# eeprom_2layer.net
KiCad netlist of a schematic drawn in EAGLE
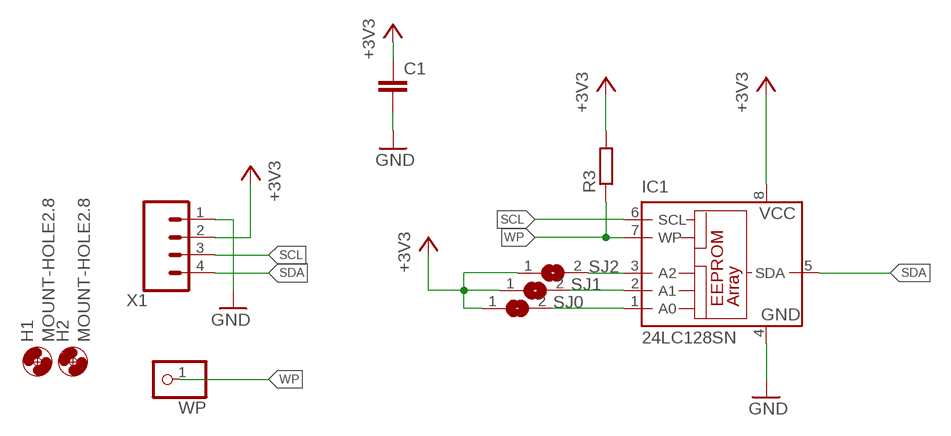
[diagram p0: schematic, sheet 1]

(export (version "E")
  (design (tool "Eeschema 10.0.6"))
  (components
    (comp (ref "C1")
      (value "C-EUC0805")
      (footprint "eagle-import:C0805")
      (libsource (lib "eagle-import") (part "C-EUC0805"))
    )
    (comp (ref "H1")
      (value "MOUNT-HOLE2.8")
      (footprint "eagle-import:2,8")
      (libsource (lib "eagle-import") (part "MOUNT-HOLE2.8"))
    )
    (comp (ref "H2")
      (value "MOUNT-HOLE2.8")
      (footprint "eagle-import:2,8")
      (libsource (lib "eagle-import") (part "MOUNT-HOLE2.8"))
    )
    (comp (ref "IC1")
      (value "24LC128SN")
      (footprint "eagle-import:SO-08")
      (fields (field (name "MF") "MICROCHIP") (field (name "MPN") "24LC128-I/SNG"))
      (libsource (lib "eagle-import") (part "24SNLC128"))
    )
    (comp (ref "R3")
      (value "R-EU_R0805")
      (footprint "eagle-import:R0805")
      (libsource (lib "eagle-import") (part "R-EU_R0805"))
    )
    (comp (ref "SJ0") (value "SJ") (footprint "eagle-import:SJ") (libsource (lib "eagle-import") (part "SJ")))
    (comp (ref "SJ1") (value "SJ") (footprint "eagle-import:SJ") (libsource (lib "eagle-import") (part "SJ")))
    (comp (ref "SJ2") (value "SJ") (footprint "eagle-import:SJ") (libsource (lib "eagle-import") (part "SJ")))
    (comp (ref "WP")
      (value "PINHD-1X1")
      (footprint "eagle-import:1X01")
      (libsource (lib "eagle-import") (part "PINHD-1X1"))
    )
    (comp (ref "X1")
      (value "JST-XH-04-PIN-ROUND-PAD")
      (footprint "eagle-import:JST-XH-04-PACKAGE-ROUND-PAD")
      (libsource (lib "eagle-import") (part "JST-XH-04-PIN-ROUND-PAD"))
    )
  )
  (nets
    (net (code "1") (name "+3V3") (class "Default")
      (node (ref "C1") (pin "1") (pinfunction "1_1") (pintype "passive"))
      (node (ref "IC1") (pin "8") (pinfunction "VCC_8") (pintype "power_in"))
      (node (ref "R3") (pin "2") (pinfunction "2_2") (pintype "passive"))
      (node (ref "SJ0") (pin "1") (pinfunction "1_1") (pintype "passive"))
      (node (ref "SJ1") (pin "1") (pinfunction "1_1") (pintype "passive"))
      (node (ref "SJ2") (pin "1") (pinfunction "1_1") (pintype "passive"))
      (node (ref "X1") (pin "2") (pinfunction "2_2") (pintype "passive"))
    )
    (net (code "2") (name "GND") (class "Default")
      (node (ref "C1") (pin "2") (pinfunction "2_2") (pintype "passive"))
      (node (ref "IC1") (pin "4") (pinfunction "GND_4") (pintype "power_in"))
      (node (ref "X1") (pin "1") (pinfunction "1_1") (pintype "passive"))
    )
    (net (code "3") (name "Net-(IC1-A0)") (class "Default")
      (node (ref "IC1") (pin "1") (pinfunction "A0_1") (pintype "input"))
      (node (ref "SJ0") (pin "2") (pinfunction "2_2") (pintype "passive"))
    )
    (net (code "4") (name "Net-(IC1-A1)") (class "Default")
      (node (ref "IC1") (pin "2") (pinfunction "A1_2") (pintype "input"))
      (node (ref "SJ1") (pin "2") (pinfunction "2_2") (pintype "passive"))
    )
    (net (code "5") (name "Net-(IC1-A2)") (class "Default")
      (node (ref "IC1") (pin "3") (pinfunction "A2_3") (pintype "input"))
      (node (ref "SJ2") (pin "2") (pinfunction "2_2") (pintype "passive"))
    )
    (net (code "6") (name "SCL") (class "Default")
      (node (ref "IC1") (pin "6") (pinfunction "SCL_6") (pintype "input"))
      (node (ref "X1") (pin "3") (pinfunction "3_3") (pintype "passive"))
    )
    (net (code "7") (name "SDA") (class "Default")
      (node (ref "IC1") (pin "5") (pinfunction "SDA_5") (pintype "bidirectional"))
      (node (ref "X1") (pin "4") (pinfunction "4_4") (pintype "passive"))
    )
    (net (code "8") (name "WP") (class "Default")
      (node (ref "IC1") (pin "7") (pinfunction "WP_7") (pintype "input"))
      (node (ref "R3") (pin "1") (pinfunction "1_1") (pintype "passive"))
      (node (ref "WP") (pin "1") (pinfunction "1_1") (pintype "passive"))
    )
  )
)
